# RC_CAR.net
KiCad netlist of a schematic drawn in Altium Designer
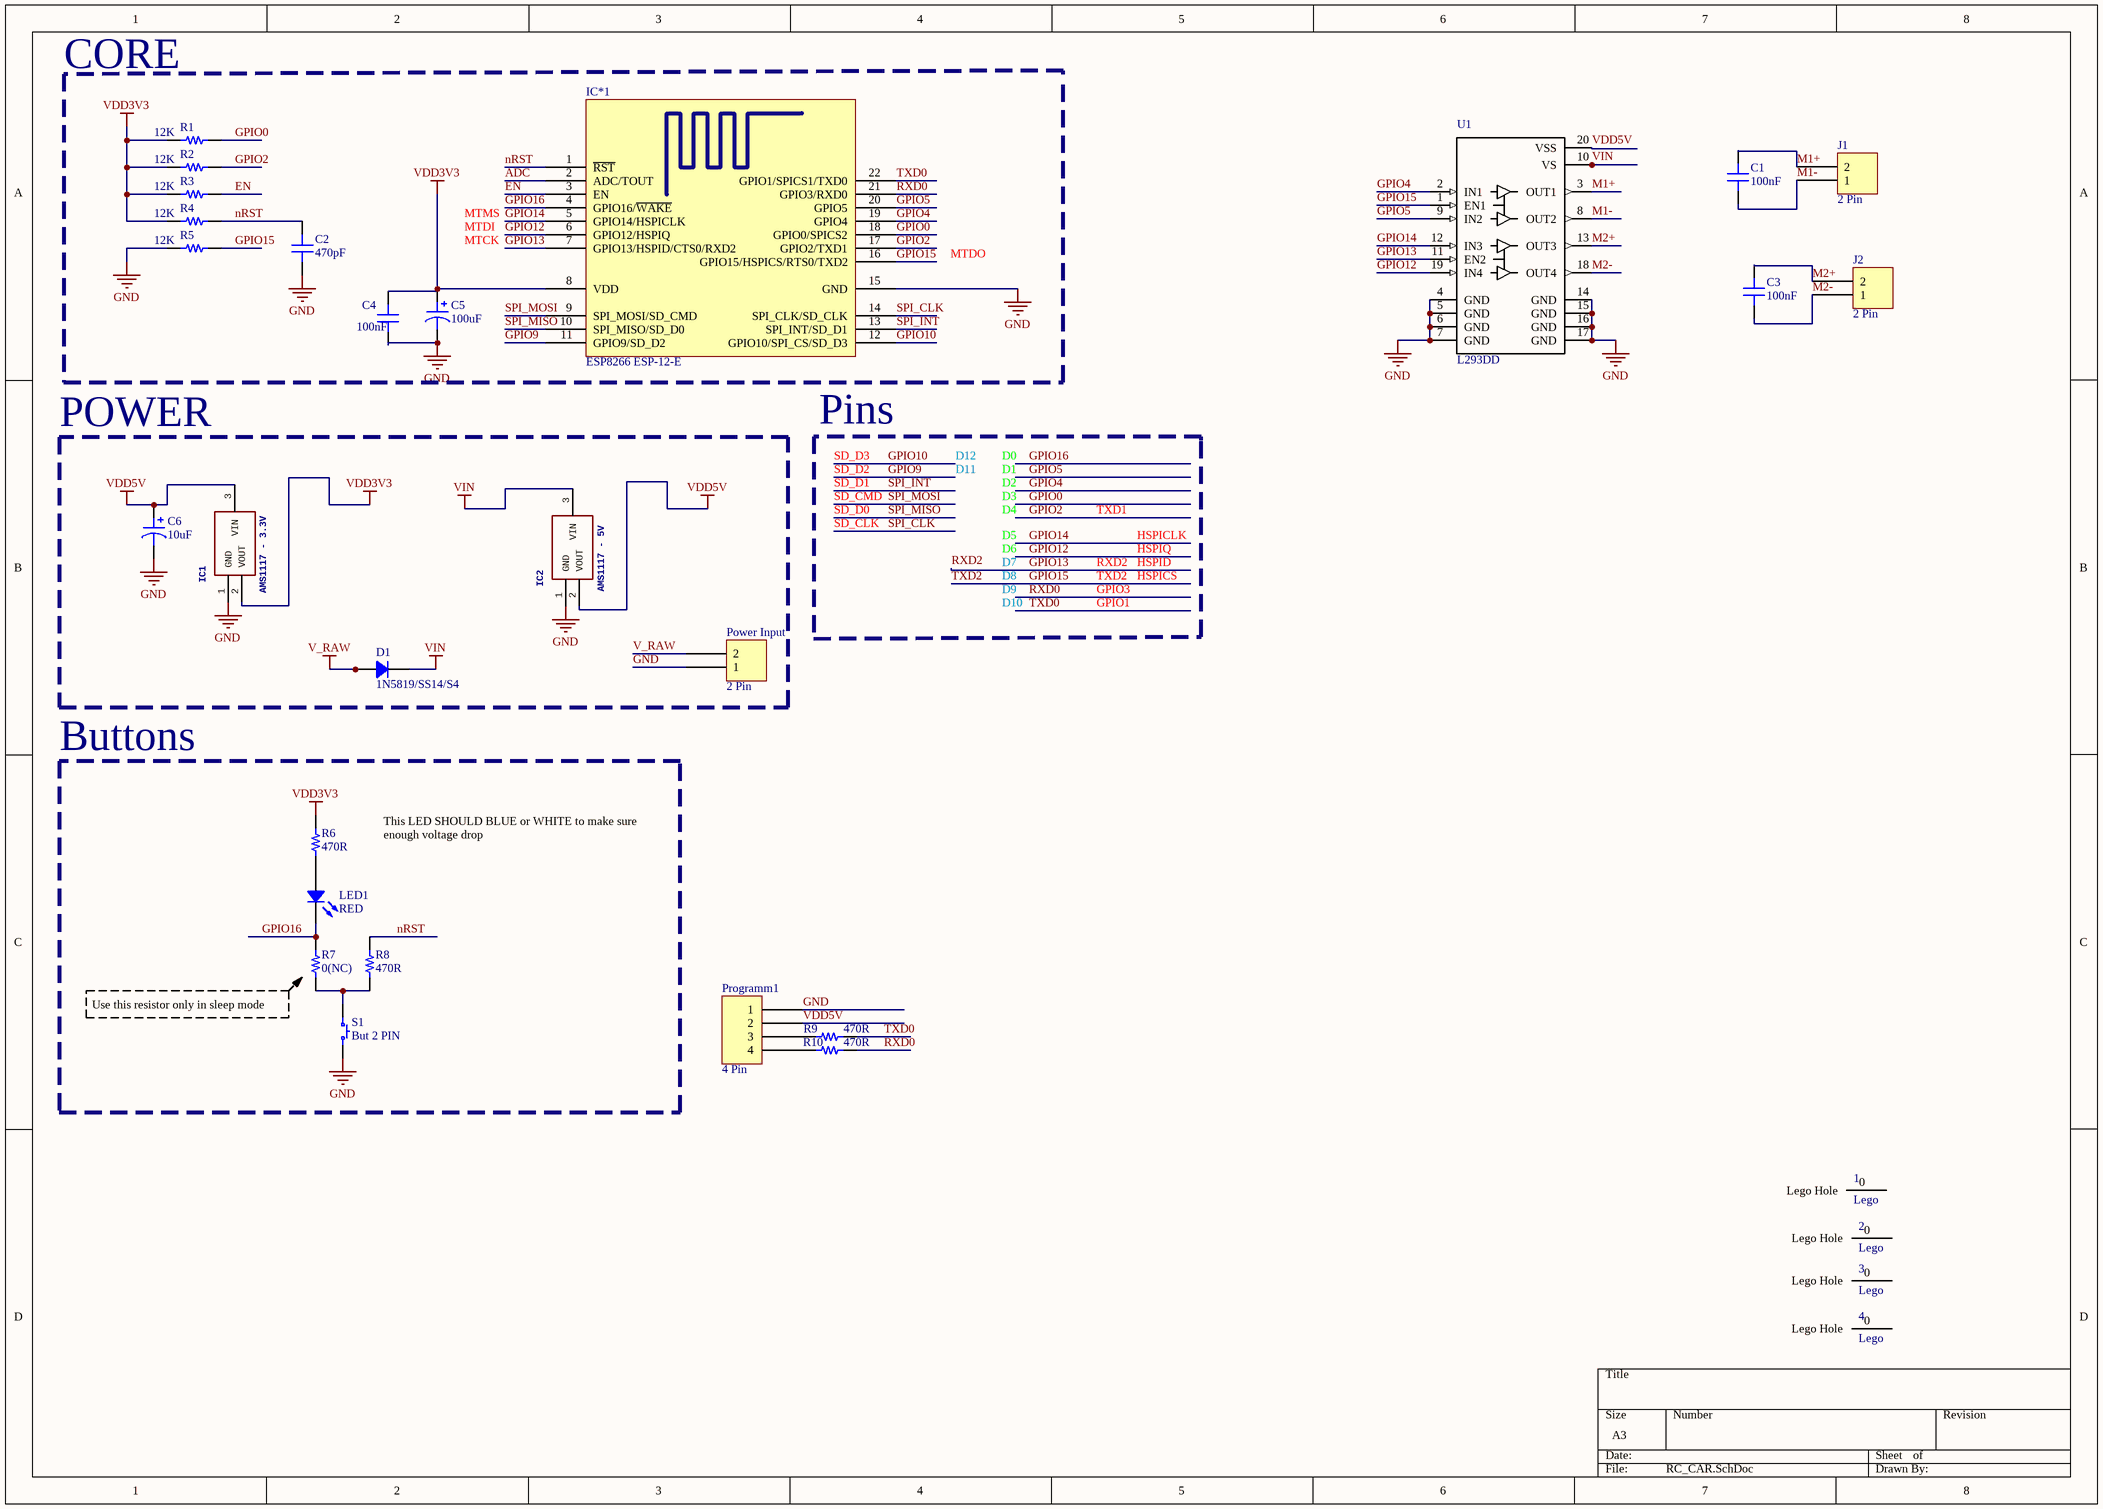
[diagram p0: RC_CAR.SchDoc]

(export (version "E")
  (design (tool "Eeschema 10.0.6"))
  (components
    (comp (ref "1") (value "Lego") (footprint "Lego Hole") (libsource (lib "Connectors") (part "Lego")))
    (comp (ref "2") (value "Lego") (footprint "Lego Hole") (libsource (lib "Connectors") (part "Lego")))
    (comp (ref "3") (value "Lego") (footprint "Lego Hole") (libsource (lib "Connectors") (part "Lego")))
    (comp (ref "4") (value "Lego") (footprint "Lego Hole") (libsource (lib "Connectors") (part "Lego")))
    (comp (ref "C1")
      (value "100nF")
      (footprint "CAP 0805/2012")
      (description "SMT Capacitor")
      (libsource (lib "Cap_Res") (part "Capacitor"))
    )
    (comp (ref "C2")
      (value "470pF")
      (footprint "CAP 0805/2012")
      (description "SMT Capacitor")
      (libsource (lib "Cap_Res") (part "Capacitor"))
    )
    (comp (ref "C3")
      (value "100nF")
      (footprint "CAP 0805/2012")
      (description "SMT Capacitor")
      (libsource (lib "Cap_Res") (part "Capacitor"))
    )
    (comp (ref "C4")
      (value "100nF")
      (footprint "CAP 0805/2012")
      (description "SMT Capacitor")
      (libsource (lib "Cap_Res") (part "Capacitor"))
    )
    (comp (ref "C5")
      (value "100uF")
      (footprint "CAP ALUM 5MM")
      (description "SMT Polarised Capacitor")
      (libsource (lib "Cap_Res") (part "Polarised Capacitor"))
    )
    (comp (ref "C6")
      (value "10uF")
      (footprint "CAP ALUM 5MM")
      (description "SMT Polarised Capacitor")
      (libsource (lib "Cap_Res") (part "Polarised Capacitor"))
    )
    (comp (ref "D1")
      (value "1N5819/SS14/S4")
      (footprint "DO214AC SMA")
      (description "Rectifier Diode")
      (libsource (lib "Cap_Res") (part "Diode"))
    )
    (comp (ref "IC*1")
      (value "ESP8266 ESP-12-E")
      (footprint "ESP8266 ESP-12-E")
      (libsource (lib "ESP8266") (part "ESP8266 ESP-12-E"))
    )
    (comp (ref "IC1")
      (value "AMS1117 - 3.3V")
      (footprint "AMS1117")
      (fields (field (name "MANUFACTURER_PART_NUMBER") "ams1117-3.3v"))
      (libsource (lib "Other") (part "AMS1117"))
    )
    (comp (ref "IC2")
      (value "AMS1117 - 5V")
      (footprint "AMS1117")
      (fields (field (name "MANUFACTURER_PART_NUMBER") "ams1117-3.3v"))
      (libsource (lib "Other") (part "AMS1117"))
    )
    (comp (ref "J1")
      (value "2 Pin")
      (footprint "Socket_Blue_2")
      (libsource (lib "Connectors") (part "2 Pin"))
    )
    (comp (ref "J2")
      (value "2 Pin")
      (footprint "Socket_Blue_2")
      (libsource (lib "Connectors") (part "2 Pin"))
    )
    (comp (ref "LED1")
      (value "RED")
      (footprint "LED 0805/2012 YELLOW")
      (description "Chip LED")
      (libsource (lib "Cap_Res") (part "LED"))
    )
    (comp (ref "Power Input")
      (value "2 Pin")
      (footprint "Socket_Blue_2")
      (libsource (lib "Connectors") (part "2 Pin"))
    )
    (comp (ref "Programm1")
      (value "4 Pin")
      (footprint "SAMTEC SSW-104-03-T-S")
      (libsource (lib "Connectors") (part "4 Pin"))
    )
    (comp (ref "R1")
      (value "12K")
      (footprint "RES 0805/2012")
      (description "SMT Resistor")
      (libsource (lib "Cap_Res") (part "Resistor"))
    )
    (comp (ref "R2")
      (value "12K")
      (footprint "RES 0805/2012")
      (description "SMT Resistor")
      (libsource (lib "Cap_Res") (part "Resistor"))
    )
    (comp (ref "R3")
      (value "12K")
      (footprint "RES 0805/2012")
      (description "SMT Resistor")
      (libsource (lib "Cap_Res") (part "Resistor"))
    )
    (comp (ref "R4")
      (value "12K")
      (footprint "RES 0805/2012")
      (description "SMT Resistor")
      (libsource (lib "Cap_Res") (part "Resistor"))
    )
    (comp (ref "R5")
      (value "12K")
      (footprint "RES 0805/2012")
      (description "SMT Resistor")
      (libsource (lib "Cap_Res") (part "Resistor"))
    )
    (comp (ref "R6")
      (value "470R")
      (footprint "RES 0805/2012")
      (description "SMT Resistor")
      (libsource (lib "Cap_Res") (part "Resistor"))
    )
    (comp (ref "R7")
      (value "0(NC)")
      (footprint "RES 0805/2012")
      (description "SMT Resistor")
      (libsource (lib "Cap_Res") (part "Resistor"))
    )
    (comp (ref "R8")
      (value "470R")
      (footprint "RES 0805/2012")
      (description "SMT Resistor")
      (libsource (lib "Cap_Res") (part "Resistor"))
    )
    (comp (ref "R9")
      (value "470R")
      (footprint "RES 0805/2012")
      (description "SMT Resistor")
      (libsource (lib "Cap_Res") (part "Resistor"))
    )
    (comp (ref "R10")
      (value "470R")
      (footprint "RES 0805/2012")
      (description "SMT Resistor")
      (libsource (lib "Cap_Res") (part "Resistor"))
    )
    (comp (ref "S1")
      (value "But 2 PIN")
      (footprint "TE FSMSMTR")
      (libsource (lib "Other") (part "But 2 PIN"))
    )
    (comp (ref "U1")
      (value "L293DD")
      (footprint "SOIC127P1030-20N")
      (description "IC MOTOR DRIVER PAR 20-SOIC")
      (fields (field (name "MF") "STMicroelectronics"))
      (libsource (lib "IC_Transistor") (part "L293DD"))
    )
  )
  (nets
    (net (code "1") (name "/ADC") (class "Default")
      (node (ref "IC*1") (pin "2") (pinfunction "ADC/TOUT_2") (pintype "passive"))
    )
    (net (code "2") (name "/EN") (class "Default")
      (node (ref "IC*1") (pin "3") (pinfunction "EN_3") (pintype "passive"))
      (node (ref "R3") (pin "1") (pinfunction "1_1") (pintype "passive"))
    )
    (net (code "3") (name "/GPIO0") (class "Default")
      (node (ref "IC*1") (pin "18") (pinfunction "GPIO0/SPICS2_18") (pintype "passive"))
      (node (ref "R1") (pin "1") (pinfunction "1_1") (pintype "passive"))
    )
    (net (code "4") (name "/GPIO2") (class "Default")
      (node (ref "IC*1") (pin "17") (pinfunction "GPIO2/TXD1_17") (pintype "passive"))
      (node (ref "R2") (pin "1") (pinfunction "1_1") (pintype "passive"))
    )
    (net (code "5") (name "/GPIO4") (class "Default")
      (node (ref "IC*1") (pin "19") (pinfunction "GPIO4_19") (pintype "passive"))
      (node (ref "U1") (pin "2") (pinfunction "IN1_2") (pintype "input"))
    )
    (net (code "6") (name "/GPIO5") (class "Default")
      (node (ref "IC*1") (pin "20") (pinfunction "GPIO5_20") (pintype "passive"))
      (node (ref "U1") (pin "9") (pinfunction "IN2_9") (pintype "input"))
    )
    (net (code "7") (name "/GPIO9") (class "Default")
      (node (ref "IC*1") (pin "11") (pinfunction "GPIO9/SD_D2_11") (pintype "passive"))
    )
    (net (code "8") (name "/GPIO10") (class "Default")
      (node (ref "IC*1") (pin "12") (pinfunction "GPIO10/SPI_CS/SD_D3_12") (pintype "passive"))
    )
    (net (code "9") (name "/GPIO12") (class "Default")
      (node (ref "IC*1") (pin "6") (pinfunction "GPIO12/HSPIQ_6") (pintype "passive"))
      (node (ref "U1") (pin "19") (pinfunction "IN4_19") (pintype "input"))
    )
    (net (code "10") (name "/GPIO13") (class "Default")
      (node (ref "IC*1") (pin "7") (pinfunction "GPIO13/HSPID/CTS0/RXD2_7") (pintype "passive"))
      (node (ref "U1") (pin "11") (pinfunction "EN2_11") (pintype "input"))
    )
    (net (code "11") (name "/GPIO14") (class "Default")
      (node (ref "IC*1") (pin "5") (pinfunction "GPIO14/HSPICLK_5") (pintype "passive"))
      (node (ref "U1") (pin "12") (pinfunction "IN3_12") (pintype "input"))
    )
    (net (code "12") (name "/GPIO15") (class "Default")
      (node (ref "IC*1") (pin "16") (pinfunction "GPIO15/HSPICS/RTS0/TXD2_16") (pintype "passive"))
      (node (ref "R5") (pin "1") (pinfunction "1_1") (pintype "passive"))
      (node (ref "U1") (pin "1") (pinfunction "EN1_1") (pintype "input"))
    )
    (net (code "13") (name "/GPIO16") (class "Default")
      (node (ref "IC*1") (pin "4") (pinfunction "GPIO16/~{WAKE}_4") (pintype "passive"))
      (node (ref "LED1") (pin "2") (pinfunction "2_2") (pintype "passive"))
      (node (ref "R7") (pin "1") (pinfunction "1_1") (pintype "passive"))
    )
    (net (code "14") (name "/M1+") (class "Default")
      (node (ref "C1") (pin "2") (pinfunction "2_2") (pintype "passive"))
      (node (ref "J1") (pin "2") (pinfunction "2_2") (pintype "passive"))
      (node (ref "U1") (pin "3") (pinfunction "OUT1_3") (pintype "output"))
    )
    (net (code "15") (name "/M1-") (class "Default")
      (node (ref "C1") (pin "1") (pinfunction "1_1") (pintype "passive"))
      (node (ref "J1") (pin "1") (pinfunction "1_1") (pintype "passive"))
      (node (ref "U1") (pin "8") (pinfunction "OUT2_8") (pintype "output"))
    )
    (net (code "16") (name "/M2+") (class "Default")
      (node (ref "C3") (pin "2") (pinfunction "2_2") (pintype "passive"))
      (node (ref "J2") (pin "2") (pinfunction "2_2") (pintype "passive"))
      (node (ref "U1") (pin "13") (pinfunction "OUT3_13") (pintype "output"))
    )
    (net (code "17") (name "/M2-") (class "Default")
      (node (ref "C3") (pin "1") (pinfunction "1_1") (pintype "passive"))
      (node (ref "J2") (pin "1") (pinfunction "1_1") (pintype "passive"))
      (node (ref "U1") (pin "18") (pinfunction "OUT4_18") (pintype "output"))
    )
    (net (code "18") (name "/RXD0") (class "Default")
      (node (ref "IC*1") (pin "21") (pinfunction "GPIO3/RXD0_21") (pintype "passive"))
      (node (ref "R10") (pin "2") (pinfunction "2_2") (pintype "passive"))
    )
    (net (code "19") (name "/SPI_CLK") (class "Default")
      (node (ref "IC*1") (pin "14") (pinfunction "SPI_CLK/SD_CLK_14") (pintype "passive"))
    )
    (net (code "20") (name "/SPI_INT") (class "Default")
      (node (ref "IC*1") (pin "13") (pinfunction "SPI_INT/SD_D1_13") (pintype "passive"))
    )
    (net (code "21") (name "/SPI_MISO") (class "Default")
      (node (ref "IC*1") (pin "10") (pinfunction "SPI_MISO/SD_D0_10") (pintype "passive"))
    )
    (net (code "22") (name "/SPI_MOSI") (class "Default")
      (node (ref "IC*1") (pin "9") (pinfunction "SPI_MOSI/SD_CMD_9") (pintype "passive"))
    )
    (net (code "23") (name "/TXD0") (class "Default")
      (node (ref "IC*1") (pin "22") (pinfunction "GPIO1/SPICS1/TXD0_22") (pintype "passive"))
      (node (ref "R9") (pin "2") (pinfunction "2_2") (pintype "passive"))
    )
    (net (code "24") (name "/nRST") (class "Default")
      (node (ref "C2") (pin "2") (pinfunction "2_2") (pintype "passive"))
      (node (ref "IC*1") (pin "1") (pinfunction "~{RST}_1") (pintype "passive"))
      (node (ref "R4") (pin "1") (pinfunction "1_1") (pintype "passive"))
      (node (ref "R8") (pin "1") (pinfunction "1_1") (pintype "passive"))
    )
    (net (code "25") (name "GND") (class "Default")
      (node (ref "C2") (pin "1") (pinfunction "1_1") (pintype "passive"))
      (node (ref "C4") (pin "1") (pinfunction "1_1") (pintype "passive"))
      (node (ref "C5") (pin "2") (pinfunction "2_2") (pintype "passive"))
      (node (ref "C6") (pin "2") (pinfunction "2_2") (pintype "passive"))
      (node (ref "IC*1") (pin "15") (pinfunction "GND_15") (pintype "passive"))
      (node (ref "IC1") (pin "1") (pinfunction "GND_1") (pintype "passive"))
      (node (ref "IC2") (pin "1") (pinfunction "GND_1") (pintype "passive"))
      (node (ref "Power Input") (pin "1") (pinfunction "1_1") (pintype "passive"))
      (node (ref "Programm1") (pin "1") (pinfunction "1_1") (pintype "passive"))
      (node (ref "R5") (pin "2") (pinfunction "2_2") (pintype "passive"))
      (node (ref "S1") (pin "2") (pinfunction "2_2") (pintype "passive"))
      (node (ref "U1") (pin "14") (pinfunction "GND_14") (pintype "passive"))
      (node (ref "U1") (pin "15") (pinfunction "GND_15") (pintype "passive"))
      (node (ref "U1") (pin "16") (pinfunction "GND_16") (pintype "passive"))
      (node (ref "U1") (pin "17") (pinfunction "GND_17") (pintype "passive"))
      (node (ref "U1") (pin "4") (pinfunction "GND_4") (pintype "passive"))
      (node (ref "U1") (pin "5") (pinfunction "GND_5") (pintype "passive"))
      (node (ref "U1") (pin "6") (pinfunction "GND_6") (pintype "passive"))
      (node (ref "U1") (pin "7") (pinfunction "GND_7") (pintype "passive"))
    )
    (net (code "26") (name "Net-(LED1-Pad1)") (class "Default")
      (node (ref "LED1") (pin "1") (pinfunction "1_1") (pintype "passive"))
      (node (ref "R6") (pin "2") (pinfunction "2_2") (pintype "passive"))
    )
    (net (code "27") (name "Net-(Programm1-Pad3)") (class "Default")
      (node (ref "Programm1") (pin "3") (pinfunction "3_3") (pintype "passive"))
      (node (ref "R9") (pin "1") (pinfunction "1_1") (pintype "passive"))
    )
    (net (code "28") (name "Net-(Programm1-Pad4)") (class "Default")
      (node (ref "Programm1") (pin "4") (pinfunction "4_4") (pintype "passive"))
      (node (ref "R10") (pin "1") (pinfunction "1_1") (pintype "passive"))
    )
    (net (code "29") (name "Net-(R7-Pad2)") (class "Default")
      (node (ref "R7") (pin "2") (pinfunction "2_2") (pintype "passive"))
      (node (ref "R8") (pin "2") (pinfunction "2_2") (pintype "passive"))
      (node (ref "S1") (pin "1") (pinfunction "1_1") (pintype "passive"))
    )
    (net (code "30") (name "VDD3V3") (class "Default")
      (node (ref "C4") (pin "2") (pinfunction "2_2") (pintype "passive"))
      (node (ref "C5") (pin "1") (pinfunction "1_1") (pintype "passive"))
      (node (ref "IC*1") (pin "8") (pinfunction "VDD_8") (pintype "passive"))
      (node (ref "IC1") (pin "2") (pinfunction "VOUT_2") (pintype "passive"))
      (node (ref "R1") (pin "2") (pinfunction "2_2") (pintype "passive"))
      (node (ref "R2") (pin "2") (pinfunction "2_2") (pintype "passive"))
      (node (ref "R3") (pin "2") (pinfunction "2_2") (pintype "passive"))
      (node (ref "R4") (pin "2") (pinfunction "2_2") (pintype "passive"))
      (node (ref "R6") (pin "1") (pinfunction "1_1") (pintype "passive"))
    )
    (net (code "31") (name "VDD5V") (class "Default")
      (node (ref "C6") (pin "1") (pinfunction "1_1") (pintype "passive"))
      (node (ref "IC1") (pin "3") (pinfunction "VIN_3") (pintype "passive"))
      (node (ref "IC2") (pin "2") (pinfunction "VOUT_2") (pintype "passive"))
      (node (ref "Programm1") (pin "2") (pinfunction "2_2") (pintype "passive"))
      (node (ref "U1") (pin "20") (pinfunction "VSS_20") (pintype "power_in"))
    )
    (net (code "32") (name "VIN") (class "Default")
      (node (ref "D1") (pin "2") (pinfunction "2_2") (pintype "passive"))
      (node (ref "IC2") (pin "3") (pinfunction "VIN_3") (pintype "passive"))
      (node (ref "U1") (pin "10") (pinfunction "VS_10") (pintype "power_in"))
    )
    (net (code "33") (name "V_RAW") (class "Default")
      (node (ref "D1") (pin "1") (pinfunction "1_1") (pintype "passive"))
      (node (ref "Power Input") (pin "2") (pinfunction "2_2") (pintype "passive"))
    )
    (net (code "34") (name "unconnected-(1-Lego_Hole-Pad0)") (class "Default")
      (node (ref "1") (pin "0") (pinfunction "Lego_Hole_0") (pintype "passive"))
    )
    (net (code "35") (name "unconnected-(2-Lego_Hole-Pad0)") (class "Default")
      (node (ref "2") (pin "0") (pinfunction "Lego_Hole_0") (pintype "passive"))
    )
    (net (code "36") (name "unconnected-(3-Lego_Hole-Pad0)") (class "Default")
      (node (ref "3") (pin "0") (pinfunction "Lego_Hole_0") (pintype "passive"))
    )
    (net (code "37") (name "unconnected-(4-Lego_Hole-Pad0)") (class "Default")
      (node (ref "4") (pin "0") (pinfunction "Lego_Hole_0") (pintype "passive"))
    )
  )
)
